# ethernet_usb.net
KiCad netlist of a schematic drawn in EAGLE
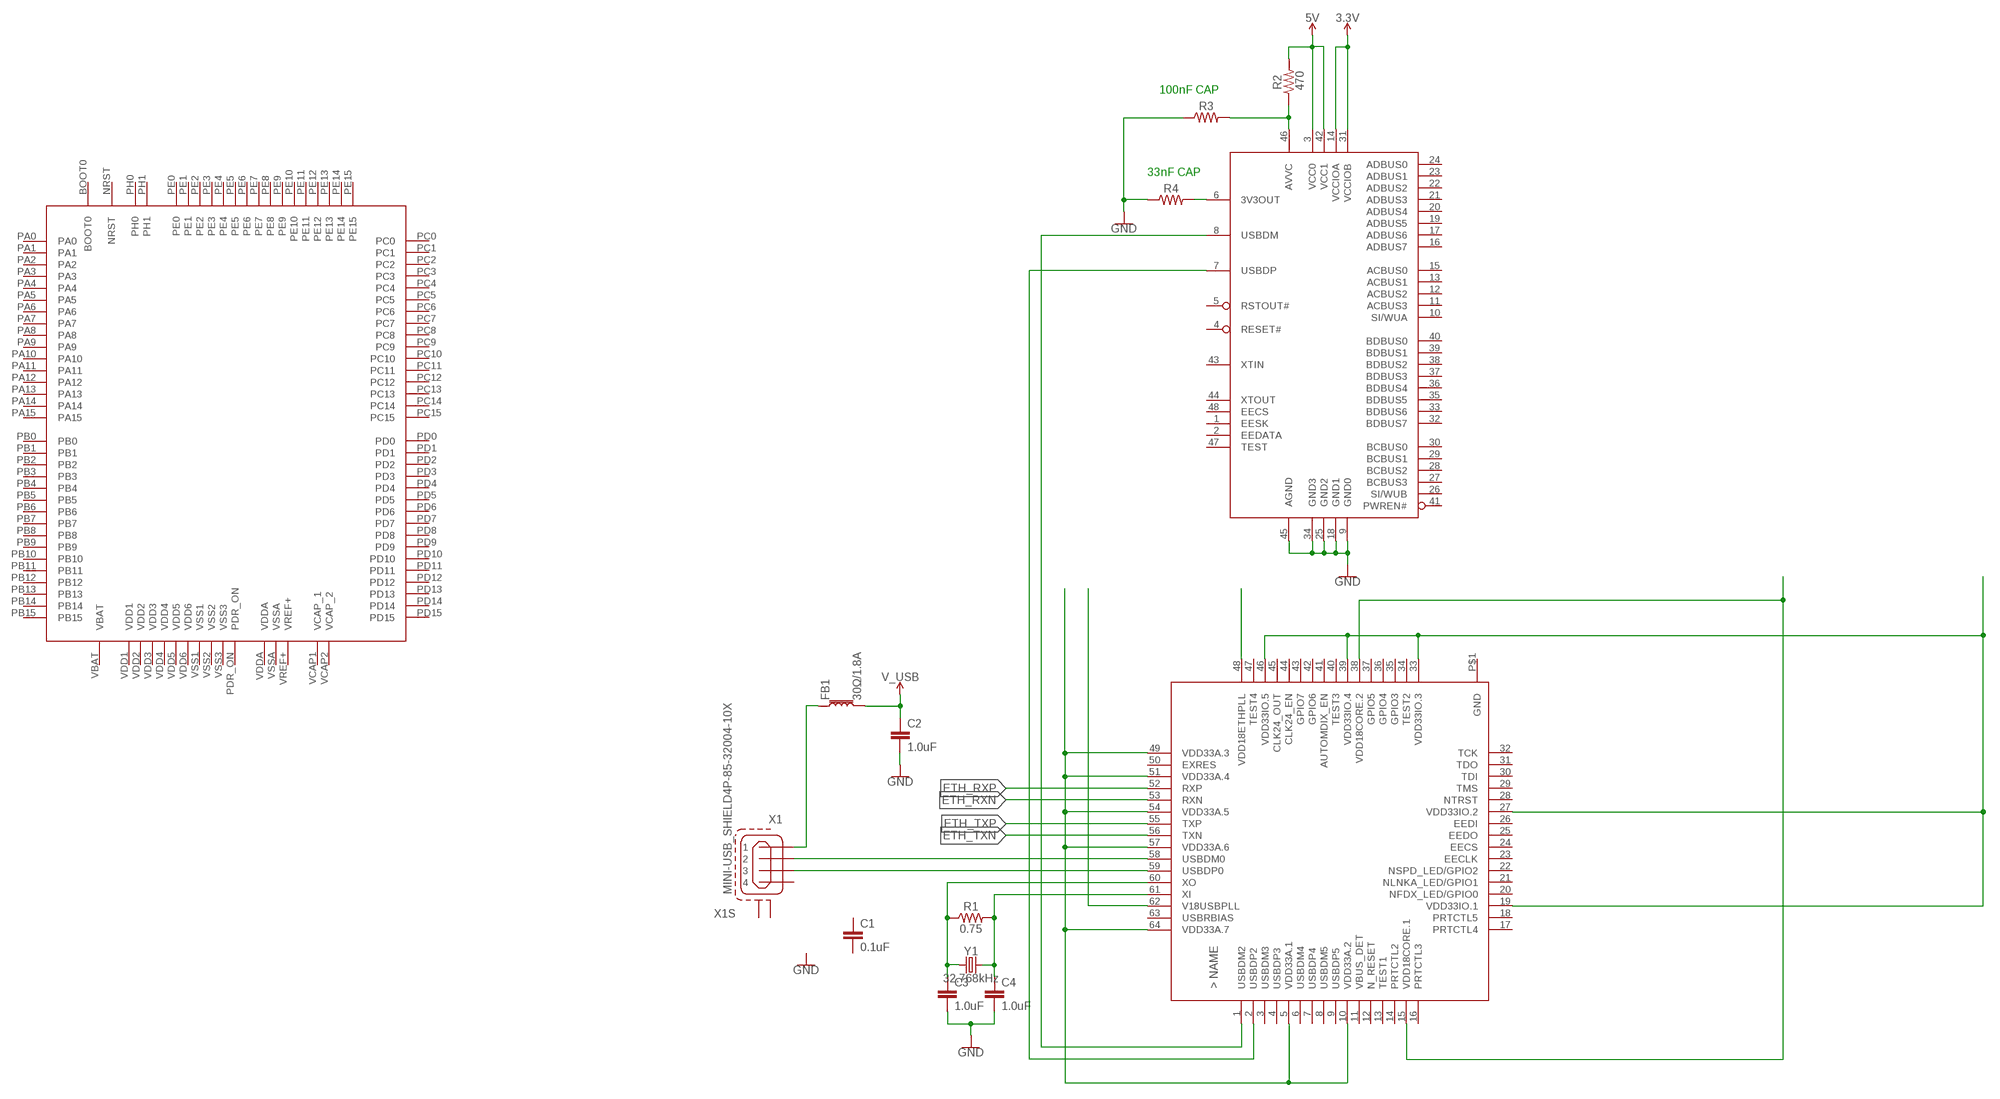
[diagram p0: schematic, sheet 1]

(export (version "E")
  (design (tool "Eeschema 10.0.6"))
  (components
    (comp (ref "C1")
      (value "0.1uF")
      (footprint "eagle-import:0603")
      (libsource (lib "eagle-import") (part "0.1UF-0603-25V-(+80/-20%)"))
    )
    (comp (ref "C2")
      (value "1.0uF")
      (footprint "eagle-import:1206")
      (libsource (lib "eagle-import") (part "1.0UF-1206-50V-10%"))
    )
    (comp (ref "C3")
      (value "1.0uF")
      (footprint "eagle-import:0805")
      (libsource (lib "eagle-import") (part "1.0UF-0805-25V-10%"))
    )
    (comp (ref "C4")
      (value "1.0uF")
      (footprint "eagle-import:0805")
      (libsource (lib "eagle-import") (part "1.0UF-0805-25V-10%"))
    )
    (comp (ref "FB1")
      (value "30Ω/1.8A")
      (footprint "eagle-import:0603")
      (libsource (lib "eagle-import") (part "FERRITE_BEAD-0603"))
    )
    (comp (ref "R1")
      (value "0.75")
      (footprint "eagle-import:0805")
      (libsource (lib "eagle-import") (part "0.75OHM-0805-1/4W-1%"))
    )
    (comp (ref "R2")
      (value "470")
      (footprint "eagle-import:0805")
      (libsource (lib "eagle-import") (part "RESISTOR0805"))
    )
    (comp (ref "R3")
      (value "RESISTOR0805")
      (footprint "eagle-import:0805")
      (libsource (lib "eagle-import") (part "RESISTOR0805"))
    )
    (comp (ref "R4")
      (value "RESISTOR0805")
      (footprint "eagle-import:0805")
      (libsource (lib "eagle-import") (part "RESISTOR0805"))
    )
    (comp (ref "U$1")
      (value "STM32F4V_100PIN_GENERIC")
      (footprint "eagle-import:LQFP100")
      (libsource (lib "eagle-import") (part "STM32F4V_100PIN_GENERIC"))
    )
    (comp (ref "U$2")
      (value "LAN9514")
      (footprint "eagle-import:QFN-64")
      (libsource (lib "eagle-import") (part "LAN9514"))
    )
    (comp (ref "U1")
      (value "FT2232L")
      (footprint "eagle-import:LQFP48")
      (libsource (lib "eagle-import") (part "FT2232L"))
    )
    (comp (ref "X1")
      (value "MINI-USB_SHIELD4P-85-32004-10X")
      (footprint "eagle-import:85-32004-10X")
      (libsource (lib "eagle-import") (part "MINI-USB_SHIELD4P-85-32004-10X"))
    )
    (comp (ref "Y1")
      (value "32.768kHz")
      (footprint "eagle-import:CRYSTAL-PTH-2X6-CYL")
      (libsource (lib "eagle-import") (part "CRYSTAL-32.768KHZPTH-2X6"))
    )
  )
  (nets
    (net (code "1") (name "3.3V") (class "Default")
      (node (ref "U1") (pin "14") (pinfunction "VCCIOA_14") (pintype "bidirectional"))
      (node (ref "U1") (pin "31") (pinfunction "VCCIOB_31") (pintype "bidirectional"))
    )
    (net (code "2") (name "5V") (class "Default")
      (node (ref "R2") (pin "2") (pinfunction "2_2") (pintype "passive"))
      (node (ref "U1") (pin "3") (pinfunction "VCC0_3") (pintype "bidirectional"))
      (node (ref "U1") (pin "42") (pinfunction "VCC1_42") (pintype "bidirectional"))
    )
    (net (code "3") (name "ETH_RXN") (class "Default")
      (node (ref "U$2") (pin "53") (pinfunction "RXN_53") (pintype "bidirectional"))
    )
    (net (code "4") (name "ETH_RXP") (class "Default")
      (node (ref "U$2") (pin "52") (pinfunction "RXP_52") (pintype "bidirectional"))
    )
    (net (code "5") (name "ETH_TXN") (class "Default")
      (node (ref "U$2") (pin "56") (pinfunction "TXN_56") (pintype "bidirectional"))
    )
    (net (code "6") (name "ETH_TXP") (class "Default")
      (node (ref "U$2") (pin "55") (pinfunction "TXP_55") (pintype "bidirectional"))
    )
    (net (code "7") (name "GND") (class "Default")
      (node (ref "C2") (pin "2") (pinfunction "2_2") (pintype "passive"))
      (node (ref "C3") (pin "2") (pinfunction "2_2") (pintype "passive"))
      (node (ref "C4") (pin "2") (pinfunction "2_2") (pintype "passive"))
      (node (ref "R3") (pin "1") (pinfunction "1_1") (pintype "passive"))
      (node (ref "R4") (pin "1") (pinfunction "1_1") (pintype "passive"))
      (node (ref "U1") (pin "18") (pinfunction "GND1_18") (pintype "bidirectional"))
      (node (ref "U1") (pin "25") (pinfunction "GND2_25") (pintype "bidirectional"))
      (node (ref "U1") (pin "34") (pinfunction "GND3_34") (pintype "bidirectional"))
      (node (ref "U1") (pin "45") (pinfunction "AGND_45") (pintype "bidirectional"))
      (node (ref "U1") (pin "9") (pinfunction "GND0_9") (pintype "bidirectional"))
    )
    (net (code "8") (name "Net-(FB1-Pad1)") (class "Default")
      (node (ref "FB1") (pin "1") (pinfunction "1_1") (pintype "passive"))
      (node (ref "X1") (pin "1") (pinfunction "1_1") (pintype "passive"))
    )
    (net (code "9") (name "Net-(U$2-USBDM0)") (class "Default")
      (node (ref "U$2") (pin "58") (pinfunction "USBDM0_58") (pintype "bidirectional"))
      (node (ref "X1") (pin "2") (pinfunction "2_2") (pintype "passive"))
    )
    (net (code "10") (name "Net-(U$2-USBDM2)") (class "Default")
      (node (ref "U$2") (pin "1") (pinfunction "USBDM2_1") (pintype "bidirectional"))
      (node (ref "U1") (pin "8") (pinfunction "USBDM_8") (pintype "bidirectional"))
    )
    (net (code "11") (name "Net-(U$2-USBDP0)") (class "Default")
      (node (ref "U$2") (pin "59") (pinfunction "USBDP0_59") (pintype "bidirectional"))
      (node (ref "X1") (pin "3") (pinfunction "3_3") (pintype "passive"))
    )
    (net (code "12") (name "Net-(U$2-USBDP2)") (class "Default")
      (node (ref "U$2") (pin "2") (pinfunction "USBDP2_2") (pintype "bidirectional"))
      (node (ref "U1") (pin "7") (pinfunction "USBDP_7") (pintype "bidirectional"))
    )
    (net (code "13") (name "Net-(U$2-VDD18CORE.1)") (class "Default")
      (node (ref "U$2") (pin "15") (pinfunction "VDD18CORE.1_15") (pintype "bidirectional"))
      (node (ref "U$2") (pin "38") (pinfunction "VDD18CORE.2_38") (pintype "bidirectional"))
    )
    (net (code "14") (name "Net-(U$2-VDD33A.1)") (class "Default")
      (node (ref "U$2") (pin "10") (pinfunction "VDD33A.2_10") (pintype "bidirectional"))
      (node (ref "U$2") (pin "49") (pinfunction "VDD33A.3_49") (pintype "bidirectional"))
      (node (ref "U$2") (pin "5") (pinfunction "VDD33A.1_5") (pintype "bidirectional"))
      (node (ref "U$2") (pin "51") (pinfunction "VDD33A.4_51") (pintype "bidirectional"))
      (node (ref "U$2") (pin "54") (pinfunction "VDD33A.5_54") (pintype "bidirectional"))
      (node (ref "U$2") (pin "57") (pinfunction "VDD33A.6_57") (pintype "bidirectional"))
      (node (ref "U$2") (pin "64") (pinfunction "VDD33A.7_64") (pintype "bidirectional"))
    )
    (net (code "15") (name "Net-(U$2-VDD33IO.1)") (class "Default")
      (node (ref "U$2") (pin "19") (pinfunction "VDD33IO.1_19") (pintype "bidirectional"))
      (node (ref "U$2") (pin "27") (pinfunction "VDD33IO.2_27") (pintype "bidirectional"))
      (node (ref "U$2") (pin "33") (pinfunction "VDD33IO.3_33") (pintype "bidirectional"))
      (node (ref "U$2") (pin "39") (pinfunction "VDD33IO.4_39") (pintype "bidirectional"))
      (node (ref "U$2") (pin "46") (pinfunction "VDD33IO.5_46") (pintype "bidirectional"))
    )
    (net (code "16") (name "Net-(U$2-XI)") (class "Default")
      (node (ref "C4") (pin "1") (pinfunction "1_1") (pintype "passive"))
      (node (ref "R1") (pin "2") (pinfunction "2_2") (pintype "passive"))
      (node (ref "U$2") (pin "61") (pinfunction "XI_61") (pintype "bidirectional"))
      (node (ref "Y1") (pin "2") (pinfunction "2_2") (pintype "passive"))
    )
    (net (code "17") (name "Net-(U$2-XO)") (class "Default")
      (node (ref "C3") (pin "1") (pinfunction "1_1") (pintype "passive"))
      (node (ref "R1") (pin "1") (pinfunction "1_1") (pintype "passive"))
      (node (ref "U$2") (pin "60") (pinfunction "XO_60") (pintype "bidirectional"))
      (node (ref "Y1") (pin "1") (pinfunction "1_1") (pintype "passive"))
    )
    (net (code "18") (name "Net-(U1-3V3OUT)") (class "Default")
      (node (ref "R4") (pin "2") (pinfunction "2_2") (pintype "passive"))
      (node (ref "U1") (pin "6") (pinfunction "3V3OUT_6") (pintype "bidirectional"))
    )
    (net (code "19") (name "Net-(U1-AVVC)") (class "Default")
      (node (ref "R2") (pin "1") (pinfunction "1_1") (pintype "passive"))
      (node (ref "R3") (pin "2") (pinfunction "2_2") (pintype "passive"))
      (node (ref "U1") (pin "46") (pinfunction "AVVC_46") (pintype "bidirectional"))
    )
    (net (code "20") (name "V_USB") (class "Default")
      (node (ref "C2") (pin "1") (pinfunction "1_1") (pintype "passive"))
      (node (ref "FB1") (pin "2") (pinfunction "2_2") (pintype "passive"))
    )
    (net (code "21") (name "unconnected-(C1-Pad1)") (class "Default")
      (node (ref "C1") (pin "1") (pinfunction "1_1") (pintype "passive"))
    )
    (net (code "22") (name "unconnected-(C1-Pad2)") (class "Default")
      (node (ref "C1") (pin "2") (pinfunction "2_2") (pintype "passive"))
    )
    (net (code "23") (name "unconnected-(U$1-PadBOOT0)") (class "Default")
      (node (ref "U$1") (pin "BOOT0") (pinfunction "BOOT0_BOOT0") (pintype "bidirectional"))
    )
    (net (code "24") (name "unconnected-(U$1-PadNRST)") (class "Default")
      (node (ref "U$1") (pin "NRST") (pinfunction "NRST_NRST") (pintype "bidirectional"))
    )
    (net (code "25") (name "unconnected-(U$1-PadPA0)") (class "Default")
      (node (ref "U$1") (pin "PA0") (pinfunction "PA0_PA0") (pintype "bidirectional"))
    )
    (net (code "26") (name "unconnected-(U$1-PadPA1)") (class "Default")
      (node (ref "U$1") (pin "PA1") (pinfunction "PA1_PA1") (pintype "bidirectional"))
    )
    (net (code "27") (name "unconnected-(U$1-PadPA2)") (class "Default")
      (node (ref "U$1") (pin "PA2") (pinfunction "PA2_PA2") (pintype "bidirectional"))
    )
    (net (code "28") (name "unconnected-(U$1-PadPA3)") (class "Default")
      (node (ref "U$1") (pin "PA3") (pinfunction "PA3_PA3") (pintype "bidirectional"))
    )
    (net (code "29") (name "unconnected-(U$1-PadPA4)") (class "Default")
      (node (ref "U$1") (pin "PA4") (pinfunction "PA4_PA4") (pintype "bidirectional"))
    )
    (net (code "30") (name "unconnected-(U$1-PadPA5)") (class "Default")
      (node (ref "U$1") (pin "PA5") (pinfunction "PA5_PA5") (pintype "bidirectional"))
    )
    (net (code "31") (name "unconnected-(U$1-PadPA6)") (class "Default")
      (node (ref "U$1") (pin "PA6") (pinfunction "PA6_PA6") (pintype "bidirectional"))
    )
    (net (code "32") (name "unconnected-(U$1-PadPA7)") (class "Default")
      (node (ref "U$1") (pin "PA7") (pinfunction "PA7_PA7") (pintype "bidirectional"))
    )
    (net (code "33") (name "unconnected-(U$1-PadPA8)") (class "Default")
      (node (ref "U$1") (pin "PA8") (pinfunction "PA8_PA8") (pintype "bidirectional"))
    )
    (net (code "34") (name "unconnected-(U$1-PadPA9)") (class "Default")
      (node (ref "U$1") (pin "PA9") (pinfunction "PA9_PA9") (pintype "bidirectional"))
    )
    (net (code "35") (name "unconnected-(U$1-PadPA10)") (class "Default")
      (node (ref "U$1") (pin "PA10") (pinfunction "PA10_PA10") (pintype "bidirectional"))
    )
    (net (code "36") (name "unconnected-(U$1-PadPA11)") (class "Default")
      (node (ref "U$1") (pin "PA11") (pinfunction "PA11_PA11") (pintype "bidirectional"))
    )
    (net (code "37") (name "unconnected-(U$1-PadPA12)") (class "Default")
      (node (ref "U$1") (pin "PA12") (pinfunction "PA12_PA12") (pintype "bidirectional"))
    )
    (net (code "38") (name "unconnected-(U$1-PadPA13)") (class "Default")
      (node (ref "U$1") (pin "PA13") (pinfunction "PA13_PA13") (pintype "bidirectional"))
    )
    (net (code "39") (name "unconnected-(U$1-PadPA14)") (class "Default")
      (node (ref "U$1") (pin "PA14") (pinfunction "PA14_PA14") (pintype "bidirectional"))
    )
    (net (code "40") (name "unconnected-(U$1-PadPA15)") (class "Default")
      (node (ref "U$1") (pin "PA15") (pinfunction "PA15_PA15") (pintype "bidirectional"))
    )
    (net (code "41") (name "unconnected-(U$1-PadPB0)") (class "Default")
      (node (ref "U$1") (pin "PB0") (pinfunction "PB0_PB0") (pintype "bidirectional"))
    )
    (net (code "42") (name "unconnected-(U$1-PadPB1)") (class "Default")
      (node (ref "U$1") (pin "PB1") (pinfunction "PB1_PB1") (pintype "bidirectional"))
    )
    (net (code "43") (name "unconnected-(U$1-PadPB2)") (class "Default")
      (node (ref "U$1") (pin "PB2") (pinfunction "PB2_PB2") (pintype "bidirectional"))
    )
    (net (code "44") (name "unconnected-(U$1-PadPB3)") (class "Default")
      (node (ref "U$1") (pin "PB3") (pinfunction "PB3_PB3") (pintype "bidirectional"))
    )
    (net (code "45") (name "unconnected-(U$1-PadPB4)") (class "Default")
      (node (ref "U$1") (pin "PB4") (pinfunction "PB4_PB4") (pintype "bidirectional"))
    )
    (net (code "46") (name "unconnected-(U$1-PadPB5)") (class "Default")
      (node (ref "U$1") (pin "PB5") (pinfunction "PB5_PB5") (pintype "bidirectional"))
    )
    (net (code "47") (name "unconnected-(U$1-PadPB6)") (class "Default")
      (node (ref "U$1") (pin "PB6") (pinfunction "PB6_PB6") (pintype "bidirectional"))
    )
    (net (code "48") (name "unconnected-(U$1-PadPB7)") (class "Default")
      (node (ref "U$1") (pin "PB7") (pinfunction "PB7_PB7") (pintype "bidirectional"))
    )
    (net (code "49") (name "unconnected-(U$1-PadPB8)") (class "Default")
      (node (ref "U$1") (pin "PB8") (pinfunction "PB8_PB8") (pintype "bidirectional"))
    )
    (net (code "50") (name "unconnected-(U$1-PadPB9)") (class "Default")
      (node (ref "U$1") (pin "PB9") (pinfunction "PB9_PB9") (pintype "bidirectional"))
    )
    (net (code "51") (name "unconnected-(U$1-PadPB10)") (class "Default")
      (node (ref "U$1") (pin "PB10") (pinfunction "PB10_PB10") (pintype "bidirectional"))
    )
    (net (code "52") (name "unconnected-(U$1-PadPB11)") (class "Default")
      (node (ref "U$1") (pin "PB11") (pinfunction "PB11_PB11") (pintype "bidirectional"))
    )
    (net (code "53") (name "unconnected-(U$1-PadPB12)") (class "Default")
      (node (ref "U$1") (pin "PB12") (pinfunction "PB12_PB12") (pintype "bidirectional"))
    )
    (net (code "54") (name "unconnected-(U$1-PadPB13)") (class "Default")
      (node (ref "U$1") (pin "PB13") (pinfunction "PB13_PB13") (pintype "bidirectional"))
    )
    (net (code "55") (name "unconnected-(U$1-PadPB14)") (class "Default")
      (node (ref "U$1") (pin "PB14") (pinfunction "PB14_PB14") (pintype "bidirectional"))
    )
    (net (code "56") (name "unconnected-(U$1-PadPB15)") (class "Default")
      (node (ref "U$1") (pin "PB15") (pinfunction "PB15_PB15") (pintype "bidirectional"))
    )
    (net (code "57") (name "unconnected-(U$1-PadPC0)") (class "Default")
      (node (ref "U$1") (pin "PC0") (pinfunction "PC0_PC0") (pintype "bidirectional"))
    )
    (net (code "58") (name "unconnected-(U$1-PadPC1)") (class "Default")
      (node (ref "U$1") (pin "PC1") (pinfunction "PC1_PC1") (pintype "bidirectional"))
    )
    (net (code "59") (name "unconnected-(U$1-PadPC2)") (class "Default")
      (node (ref "U$1") (pin "PC2") (pinfunction "PC2_PC2") (pintype "bidirectional"))
    )
    (net (code "60") (name "unconnected-(U$1-PadPC3)") (class "Default")
      (node (ref "U$1") (pin "PC3") (pinfunction "PC3_PC3") (pintype "bidirectional"))
    )
    (net (code "61") (name "unconnected-(U$1-PadPC4)") (class "Default")
      (node (ref "U$1") (pin "PC4") (pinfunction "PC4_PC4") (pintype "bidirectional"))
    )
    (net (code "62") (name "unconnected-(U$1-PadPC5)") (class "Default")
      (node (ref "U$1") (pin "PC5") (pinfunction "PC5_PC5") (pintype "bidirectional"))
    )
    (net (code "63") (name "unconnected-(U$1-PadPC6)") (class "Default")
      (node (ref "U$1") (pin "PC6") (pinfunction "PC6_PC6") (pintype "bidirectional"))
    )
    (net (code "64") (name "unconnected-(U$1-PadPC7)") (class "Default")
      (node (ref "U$1") (pin "PC7") (pinfunction "PC7_PC7") (pintype "bidirectional"))
    )
    (net (code "65") (name "unconnected-(U$1-PadPC8)") (class "Default")
      (node (ref "U$1") (pin "PC8") (pinfunction "PC8_PC8") (pintype "bidirectional"))
    )
    (net (code "66") (name "unconnected-(U$1-PadPC9)") (class "Default")
      (node (ref "U$1") (pin "PC9") (pinfunction "PC9_PC9") (pintype "bidirectional"))
    )
    (net (code "67") (name "unconnected-(U$1-PadPC10)") (class "Default")
      (node (ref "U$1") (pin "PC10") (pinfunction "PC10_PC10") (pintype "bidirectional"))
    )
    (net (code "68") (name "unconnected-(U$1-PadPC11)") (class "Default")
      (node (ref "U$1") (pin "PC11") (pinfunction "PC11_PC11") (pintype "bidirectional"))
    )
    (net (code "69") (name "unconnected-(U$1-PadPC12)") (class "Default")
      (node (ref "U$1") (pin "PC12") (pinfunction "PC12_PC12") (pintype "bidirectional"))
    )
    (net (code "70") (name "unconnected-(U$1-PadPC13)") (class "Default")
      (node (ref "U$1") (pin "PC13") (pinfunction "PC13_PC13") (pintype "bidirectional"))
    )
    (net (code "71") (name "unconnected-(U$1-PadPC14)") (class "Default")
      (node (ref "U$1") (pin "PC14") (pinfunction "PC14_PC14") (pintype "bidirectional"))
    )
    (net (code "72") (name "unconnected-(U$1-PadPC15)") (class "Default")
      (node (ref "U$1") (pin "PC15") (pinfunction "PC15_PC15") (pintype "bidirectional"))
    )
    (net (code "73") (name "unconnected-(U$1-PadPD0)") (class "Default")
      (node (ref "U$1") (pin "PD0") (pinfunction "PD0_PD0") (pintype "bidirectional"))
    )
    (net (code "74") (name "unconnected-(U$1-PadPD1)") (class "Default")
      (node (ref "U$1") (pin "PD1") (pinfunction "PD1_PD1") (pintype "bidirectional"))
    )
    (net (code "75") (name "unconnected-(U$1-PadPD2)") (class "Default")
      (node (ref "U$1") (pin "PD2") (pinfunction "PD2_PD2") (pintype "bidirectional"))
    )
    (net (code "76") (name "unconnected-(U$1-PadPD3)") (class "Default")
      (node (ref "U$1") (pin "PD3") (pinfunction "PD3_PD3") (pintype "bidirectional"))
    )
    (net (code "77") (name "unconnected-(U$1-PadPD4)") (class "Default")
      (node (ref "U$1") (pin "PD4") (pinfunction "PD4_PD4") (pintype "bidirectional"))
    )
    (net (code "78") (name "unconnected-(U$1-PadPD5)") (class "Default")
      (node (ref "U$1") (pin "PD5") (pinfunction "PD5_PD5") (pintype "bidirectional"))
    )
    (net (code "79") (name "unconnected-(U$1-PadPD6)") (class "Default")
      (node (ref "U$1") (pin "PD6") (pinfunction "PD6_PD6") (pintype "bidirectional"))
    )
    (net (code "80") (name "unconnected-(U$1-PadPD7)") (class "Default")
      (node (ref "U$1") (pin "PD7") (pinfunction "PD7_PD7") (pintype "bidirectional"))
    )
    (net (code "81") (name "unconnected-(U$1-PadPD8)") (class "Default")
      (node (ref "U$1") (pin "PD8") (pinfunction "PD8_PD8") (pintype "bidirectional"))
    )
    (net (code "82") (name "unconnected-(U$1-PadPD9)") (class "Default")
      (node (ref "U$1") (pin "PD9") (pinfunction "PD9_PD9") (pintype "bidirectional"))
    )
    (net (code "83") (name "unconnected-(U$1-PadPD10)") (class "Default")
      (node (ref "U$1") (pin "PD10") (pinfunction "PD10_PD10") (pintype "bidirectional"))
    )
    (net (code "84") (name "unconnected-(U$1-PadPD11)") (class "Default")
      (node (ref "U$1") (pin "PD11") (pinfunction "PD11_PD11") (pintype "bidirectional"))
    )
    (net (code "85") (name "unconnected-(U$1-PadPD12)") (class "Default")
      (node (ref "U$1") (pin "PD12") (pinfunction "PD12_PD12") (pintype "bidirectional"))
    )
    (net (code "86") (name "unconnected-(U$1-PadPD13)") (class "Default")
      (node (ref "U$1") (pin "PD13") (pinfunction "PD13_PD13") (pintype "bidirectional"))
    )
    (net (code "87") (name "unconnected-(U$1-PadPD14)") (class "Default")
      (node (ref "U$1") (pin "PD14") (pinfunction "PD14_PD14") (pintype "bidirectional"))
    )
    (net (code "88") (name "unconnected-(U$1-PadPD15)") (class "Default")
      (node (ref "U$1") (pin "PD15") (pinfunction "PD15_PD15") (pintype "bidirectional"))
    )
    (net (code "89") (name "unconnected-(U$1-PadPDR_ON)") (class "Default")
      (node (ref "U$1") (pin "PDR_ON") (pinfunction "PDR_ON_PDR_ON") (pintype "bidirectional"))
    )
    (net (code "90") (name "unconnected-(U$1-PadPE0)") (class "Default")
      (node (ref "U$1") (pin "PE0") (pinfunction "PE0_PE0") (pintype "bidirectional"))
    )
    (net (code "91") (name "unconnected-(U$1-PadPE1)") (class "Default")
      (node (ref "U$1") (pin "PE1") (pinfunction "PE1_PE1") (pintype "bidirectional"))
    )
    (net (code "92") (name "unconnected-(U$1-PadPE2)") (class "Default")
      (node (ref "U$1") (pin "PE2") (pinfunction "PE2_PE2") (pintype "bidirectional"))
    )
    (net (code "93") (name "unconnected-(U$1-PadPE3)") (class "Default")
      (node (ref "U$1") (pin "PE3") (pinfunction "PE3_PE3") (pintype "bidirectional"))
    )
    (net (code "94") (name "unconnected-(U$1-PadPE4)") (class "Default")
      (node (ref "U$1") (pin "PE4") (pinfunction "PE4_PE4") (pintype "bidirectional"))
    )
    (net (code "95") (name "unconnected-(U$1-PadPE5)") (class "Default")
      (node (ref "U$1") (pin "PE5") (pinfunction "PE5_PE5") (pintype "bidirectional"))
    )
    (net (code "96") (name "unconnected-(U$1-PadPE6)") (class "Default")
      (node (ref "U$1") (pin "PE6") (pinfunction "PE6_PE6") (pintype "bidirectional"))
    )
    (net (code "97") (name "unconnected-(U$1-PadPE7)") (class "Default")
      (node (ref "U$1") (pin "PE7") (pinfunction "PE7_PE7") (pintype "bidirectional"))
    )
    (net (code "98") (name "unconnected-(U$1-PadPE8)") (class "Default")
      (node (ref "U$1") (pin "PE8") (pinfunction "PE8_PE8") (pintype "bidirectional"))
    )
    (net (code "99") (name "unconnected-(U$1-PadPE9)") (class "Default")
      (node (ref "U$1") (pin "PE9") (pinfunction "PE9_PE9") (pintype "bidirectional"))
    )
    (net (code "100") (name "unconnected-(U$1-PadPE10)") (class "Default")
      (node (ref "U$1") (pin "PE10") (pinfunction "PE10_PE10") (pintype "bidirectional"))
    )
    (net (code "101") (name "unconnected-(U$1-PadPE11)") (class "Default")
      (node (ref "U$1") (pin "PE11") (pinfunction "PE11_PE11") (pintype "bidirectional"))
    )
    (net (code "102") (name "unconnected-(U$1-PadPE12)") (class "Default")
      (node (ref "U$1") (pin "PE12") (pinfunction "PE12_PE12") (pintype "bidirectional"))
    )
    (net (code "103") (name "unconnected-(U$1-PadPE13)") (class "Default")
      (node (ref "U$1") (pin "PE13") (pinfunction "PE13_PE13") (pintype "bidirectional"))
    )
    (net (code "104") (name "unconnected-(U$1-PadPE14)") (class "Default")
      (node (ref "U$1") (pin "PE14") (pinfunction "PE14_PE14") (pintype "bidirectional"))
    )
    (net (code "105") (name "unconnected-(U$1-PadPE15)") (class "Default")
      (node (ref "U$1") (pin "PE15") (pinfunction "PE15_PE15") (pintype "bidirectional"))
    )
    (net (code "106") (name "unconnected-(U$1-PadPH0)") (class "Default")
      (node (ref "U$1") (pin "PH0") (pinfunction "PH0_PH0") (pintype "bidirectional"))
    )
    (net (code "107") (name "unconnected-(U$1-PadPH1)") (class "Default")
      (node (ref "U$1") (pin "PH1") (pinfunction "PH1_PH1") (pintype "bidirectional"))
    )
    (net (code "108") (name "unconnected-(U$1-PadVBAT)") (class "Default")
      (node (ref "U$1") (pin "VBAT") (pinfunction "VBAT_VBAT") (pintype "bidirectional"))
    )
    (net (code "109") (name "unconnected-(U$1-PadVDD1)") (class "Default")
      (node (ref "U$1") (pin "VDD1") (pinfunction "VDD1_VDD1") (pintype "bidirectional"))
    )
    (net (code "110") (name "unconnected-(U$1-PadVDD2)") (class "Default")
      (node (ref "U$1") (pin "VDD2") (pinfunction "VDD2_VDD2") (pintype "bidirectional"))
    )
    (net (code "111") (name "unconnected-(U$1-PadVDD3)") (class "Default")
      (node (ref "U$1") (pin "VDD3") (pinfunction "VDD3_VDD3") (pintype "bidirectional"))
    )
    (net (code "112") (name "unconnected-(U$1-PadVDD4)") (class "Default")
      (node (ref "U$1") (pin "VDD4") (pinfunction "VDD4_VDD4") (pintype "bidirectional"))
    )
    (net (code "113") (name "unconnected-(U$1-PadVDD5)") (class "Default")
      (node (ref "U$1") (pin "VDD5") (pinfunction "VDD5_VDD5") (pintype "bidirectional"))
    )
    (net (code "114") (name "unconnected-(U$1-PadVDD6)") (class "Default")
      (node (ref "U$1") (pin "VDD6") (pinfunction "VDD6_VDD6") (pintype "bidirectional"))
    )
    (net (code "115") (name "unconnected-(U$1-PadVDDA)") (class "Default")
      (node (ref "U$1") (pin "VDDA") (pinfunction "VDDA_VDDA") (pintype "bidirectional"))
    )
    (net (code "116") (name "unconnected-(U$1-PadVREF+)") (class "Default")
      (node (ref "U$1") (pin "VREF+") (pinfunction "VREF+_VREF+") (pintype "bidirectional"))
    )
    (net (code "117") (name "unconnected-(U$1-PadVSS1)") (class "Default")
      (node (ref "U$1") (pin "VSS1") (pinfunction "VSS1_VSS1") (pintype "bidirectional"))
    )
    (net (code "118") (name "unconnected-(U$1-PadVSS2)") (class "Default")
      (node (ref "U$1") (pin "VSS2") (pinfunction "VSS2_VSS2") (pintype "bidirectional"))
    )
    (net (code "119") (name "unconnected-(U$1-PadVSS3)") (class "Default")
      (node (ref "U$1") (pin "VSS3") (pinfunction "VSS3_VSS3") (pintype "bidirectional"))
    )
    (net (code "120") (name "unconnected-(U$1-PadVSSA)") (class "Default")
      (node (ref "U$1") (pin "VSSA") (pinfunction "VSSA_VSSA") (pintype "bidirectional"))
    )
    (net (code "121") (name "unconnected-(U$1-VCAP_1-PadVCAP1)") (class "Default")
      (node (ref "U$1") (pin "VCAP1") (pinfunction "VCAP_1_VCAP1") (pintype "bidirectional"))
    )
    (net (code "122") (name "unconnected-(U$1-VCAP_2-PadVCAP2)") (class "Default")
      (node (ref "U$1") (pin "VCAP2") (pinfunction "VCAP_2_VCAP2") (pintype "bidirectional"))
    )
    (net (code "123") (name "unconnected-(U$2-AUTOMDIX_EN-Pad41)") (class "Default")
      (node (ref "U$2") (pin "41") (pinfunction "AUTOMDIX_EN_41") (pintype "bidirectional"))
    )
    (net (code "124") (name "unconnected-(U$2-CLK24_EN-Pad44)") (class "Default")
      (node (ref "U$2") (pin "44") (pinfunction "CLK24_EN_44") (pintype "bidirectional"))
    )
    (net (code "125") (name "unconnected-(U$2-CLK24_OUT-Pad45)") (class "Default")
      (node (ref "U$2") (pin "45") (pinfunction "CLK24_OUT_45") (pintype "bidirectional"))
    )
    (net (code "126") (name "unconnected-(U$2-EECLK-Pad23)") (class "Default")
      (node (ref "U$2") (pin "23") (pinfunction "EECLK_23") (pintype "bidirectional"))
    )
    (net (code "127") (name "unconnected-(U$2-EECS-Pad24)") (class "Default")
      (node (ref "U$2") (pin "24") (pinfunction "EECS_24") (pintype "bidirectional"))
    )
    (net (code "128") (name "unconnected-(U$2-EEDI-Pad26)") (class "Default")
      (node (ref "U$2") (pin "26") (pinfunction "EEDI_26") (pintype "bidirectional"))
    )
    (net (code "129") (name "unconnected-(U$2-EEDO-Pad25)") (class "Default")
      (node (ref "U$2") (pin "25") (pinfunction "EEDO_25") (pintype "bidirectional"))
    )
    (net (code "130") (name "unconnected-(U$2-EXRES-Pad50)") (class "Default")
      (node (ref "U$2") (pin "50") (pinfunction "EXRES_50") (pintype "bidirectional"))
    )
    (net (code "131") (name "unconnected-(U$2-GND-PadP$1)") (class "Default")
      (node (ref "U$2") (pin "P$1") (pinfunction "GND_P$1") (pintype "bidirectional"))
    )
    (net (code "132") (name "unconnected-(U$2-GPIO3-Pad35)") (class "Default")
      (node (ref "U$2") (pin "35") (pinfunction "GPIO3_35") (pintype "bidirectional"))
    )
    (net (code "133") (name "unconnected-(U$2-GPIO4-Pad36)") (class "Default")
      (node (ref "U$2") (pin "36") (pinfunction "GPIO4_36") (pintype "bidirectional"))
    )
    (net (code "134") (name "unconnected-(U$2-GPIO5-Pad37)") (class "Default")
      (node (ref "U$2") (pin "37") (pinfunction "GPIO5_37") (pintype "bidirectional"))
    )
    (net (code "135") (name "unconnected-(U$2-GPIO6-Pad42)") (class "Default")
      (node (ref "U$2") (pin "42") (pinfunction "GPIO6_42") (pintype "bidirectional"))
    )
    (net (code "136") (name "unconnected-(U$2-GPIO7-Pad43)") (class "Default")
      (node (ref "U$2") (pin "43") (pinfunction "GPIO7_43") (pintype "bidirectional"))
    )
    (net (code "137") (name "unconnected-(U$2-NFDX_LED{slash}GPIO0-Pad20)") (class "Default")
      (node (ref "U$2") (pin "20") (pinfunction "NFDX_LED/GPIO0_20") (pintype "bidirectional"))
    )
    (net (code "138") (name "unconnected-(U$2-NLNKA_LED{slash}GPIO1-Pad21)") (class "Default")
      (node (ref "U$2") (pin "21") (pinfunction "NLNKA_LED/GPIO1_21") (pintype "bidirectional"))
    )
    (net (code "139") (name "unconnected-(U$2-NSPD_LED{slash}GPIO2-Pad22)") (class "Default")
      (node (ref "U$2") (pin "22") (pinfunction "NSPD_LED/GPIO2_22") (pintype "bidirectional"))
    )
    (net (code "140") (name "unconnected-(U$2-NTRST-Pad28)") (class "Default")
      (node (ref "U$2") (pin "28") (pinfunction "NTRST_28") (pintype "bidirectional"))
    )
    (net (code "141") (name "unconnected-(U$2-N_RESET-Pad12)") (class "Default")
      (node (ref "U$2") (pin "12") (pinfunction "N_RESET_12") (pintype "bidirectional"))
    )
    (net (code "142") (name "unconnected-(U$2-PRTCTL2-Pad14)") (class "Default")
      (node (ref "U$2") (pin "14") (pinfunction "PRTCTL2_14") (pintype "bidirectional"))
    )
    (net (code "143") (name "unconnected-(U$2-PRTCTL3-Pad16)") (class "Default")
      (node (ref "U$2") (pin "16") (pinfunction "PRTCTL3_16") (pintype "bidirectional"))
    )
    (net (code "144") (name "unconnected-(U$2-PRTCTL4-Pad17)") (class "Default")
      (node (ref "U$2") (pin "17") (pinfunction "PRTCTL4_17") (pintype "bidirectional"))
    )
    (net (code "145") (name "unconnected-(U$2-PRTCTL5-Pad18)") (class "Default")
      (node (ref "U$2") (pin "18") (pinfunction "PRTCTL5_18") (pintype "bidirectional"))
    )
    (net (code "146") (name "unconnected-(U$2-TCK-Pad32)") (class "Default")
      (node (ref "U$2") (pin "32") (pinfunction "TCK_32") (pintype "bidirectional"))
    )
    (net (code "147") (name "unconnected-(U$2-TDI-Pad30)") (class "Default")
      (node (ref "U$2") (pin "30") (pinfunction "TDI_30") (pintype "bidirectional"))
    )
    (net (code "148") (name "unconnected-(U$2-TDO-Pad31)") (class "Default")
      (node (ref "U$2") (pin "31") (pinfunction "TDO_31") (pintype "bidirectional"))
    )
    (net (code "149") (name "unconnected-(U$2-TEST1-Pad13)") (class "Default")
      (node (ref "U$2") (pin "13") (pinfunction "TEST1_13") (pintype "bidirectional"))
    )
    (net (code "150") (name "unconnected-(U$2-TEST2-Pad34)") (class "Default")
      (node (ref "U$2") (pin "34") (pinfunction "TEST2_34") (pintype "bidirectional"))
    )
    (net (code "151") (name "unconnected-(U$2-TEST3-Pad40)") (class "Default")
      (node (ref "U$2") (pin "40") (pinfunction "TEST3_40") (pintype "bidirectional"))
    )
    (net (code "152") (name "unconnected-(U$2-TEST4-Pad47)") (class "Default")
      (node (ref "U$2") (pin "47") (pinfunction "TEST4_47") (pintype "bidirectional"))
    )
    (net (code "153") (name "unconnected-(U$2-TMS-Pad29)") (class "Default")
      (node (ref "U$2") (pin "29") (pinfunction "TMS_29") (pintype "bidirectional"))
    )
    (net (code "154") (name "unconnected-(U$2-USBDM3-Pad3)") (class "Default")
      (node (ref "U$2") (pin "3") (pinfunction "USBDM3_3") (pintype "bidirectional"))
    )
    (net (code "155") (name "unconnected-(U$2-USBDM4-Pad6)") (class "Default")
      (node (ref "U$2") (pin "6") (pinfunction "USBDM4_6") (pintype "bidirectional"))
    )
    (net (code "156") (name "unconnected-(U$2-USBDM5-Pad8)") (class "Default")
      (node (ref "U$2") (pin "8") (pinfunction "USBDM5_8") (pintype "bidirectional"))
    )
    (net (code "157") (name "unconnected-(U$2-USBDP3-Pad4)") (class "Default")
      (node (ref "U$2") (pin "4") (pinfunction "USBDP3_4") (pintype "bidirectional"))
    )
    (net (code "158") (name "unconnected-(U$2-USBDP4-Pad7)") (class "Default")
      (node (ref "U$2") (pin "7") (pinfunction "USBDP4_7") (pintype "bidirectional"))
    )
    (net (code "159") (name "unconnected-(U$2-USBDP5-Pad9)") (class "Default")
      (node (ref "U$2") (pin "9") (pinfunction "USBDP5_9") (pintype "bidirectional"))
    )
    (net (code "160") (name "unconnected-(U$2-USBRBIAS-Pad63)") (class "Default")
      (node (ref "U$2") (pin "63") (pinfunction "USBRBIAS_63") (pintype "bidirectional"))
    )
    (net (code "161") (name "unconnected-(U$2-V18USBPLL-Pad62)") (class "Default")
      (node (ref "U$2") (pin "62") (pinfunction "V18USBPLL_62") (pintype "bidirectional"))
    )
    (net (code "162") (name "unconnected-(U$2-VBUS_DET-Pad11)") (class "Default")
      (node (ref "U$2") (pin "11") (pinfunction "VBUS_DET_11") (pintype "bidirectional"))
    )
    (net (code "163") (name "unconnected-(U$2-VDD18ETHPLL-Pad48)") (class "Default")
      (node (ref "U$2") (pin "48") (pinfunction "VDD18ETHPLL_48") (pintype "bidirectional"))
    )
    (net (code "164") (name "unconnected-(U1-ACBUS0-Pad15)") (class "Default")
      (node (ref "U1") (pin "15") (pinfunction "ACBUS0_15") (pintype "bidirectional"))
    )
    (net (code "165") (name "unconnected-(U1-ACBUS1-Pad13)") (class "Default")
      (node (ref "U1") (pin "13") (pinfunction "ACBUS1_13") (pintype "bidirectional"))
    )
    (net (code "166") (name "unconnected-(U1-ACBUS2-Pad12)") (class "Default")
      (node (ref "U1") (pin "12") (pinfunction "ACBUS2_12") (pintype "bidirectional"))
    )
    (net (code "167") (name "unconnected-(U1-ACBUS3-Pad11)") (class "Default")
      (node (ref "U1") (pin "11") (pinfunction "ACBUS3_11") (pintype "bidirectional"))
    )
    (net (code "168") (name "unconnected-(U1-ADBUS0-Pad24)") (class "Default")
      (node (ref "U1") (pin "24") (pinfunction "ADBUS0_24") (pintype "bidirectional"))
    )
    (net (code "169") (name "unconnected-(U1-ADBUS1-Pad23)") (class "Default")
      (node (ref "U1") (pin "23") (pinfunction "ADBUS1_23") (pintype "bidirectional"))
    )
    (net (code "170") (name "unconnected-(U1-ADBUS2-Pad22)") (class "Default")
      (node (ref "U1") (pin "22") (pinfunction "ADBUS2_22") (pintype "bidirectional"))
    )
    (net (code "171") (name "unconnected-(U1-ADBUS3-Pad21)") (class "Default")
      (node (ref "U1") (pin "21") (pinfunction "ADBUS3_21") (pintype "bidirectional"))
    )
    (net (code "172") (name "unconnected-(U1-ADBUS4-Pad20)") (class "Default")
      (node (ref "U1") (pin "20") (pinfunction "ADBUS4_20") (pintype "bidirectional"))
    )
    (net (code "173") (name "unconnected-(U1-ADBUS5-Pad19)") (class "Default")
      (node (ref "U1") (pin "19") (pinfunction "ADBUS5_19") (pintype "bidirectional"))
    )
    (net (code "174") (name "unconnected-(U1-ADBUS6-Pad17)") (class "Default")
      (node (ref "U1") (pin "17") (pinfunction "ADBUS6_17") (pintype "bidirectional"))
    )
    (net (code "175") (name "unconnected-(U1-ADBUS7-Pad16)") (class "Default")
      (node (ref "U1") (pin "16") (pinfunction "ADBUS7_16") (pintype "bidirectional"))
    )
    (net (code "176") (name "unconnected-(U1-BCBUS0-Pad30)") (class "Default")
      (node (ref "U1") (pin "30") (pinfunction "BCBUS0_30") (pintype "bidirectional"))
    )
    (net (code "177") (name "unconnected-(U1-BCBUS1-Pad29)") (class "Default")
      (node (ref "U1") (pin "29") (pinfunction "BCBUS1_29") (pintype "bidirectional"))
    )
    (net (code "178") (name "unconnected-(U1-BCBUS2-Pad28)") (class "Default")
      (node (ref "U1") (pin "28") (pinfunction "BCBUS2_28") (pintype "bidirectional"))
    )
    (net (code "179") (name "unconnected-(U1-BCBUS3-Pad27)") (class "Default")
      (node (ref "U1") (pin "27") (pinfunction "BCBUS3_27") (pintype "bidirectional"))
    )
    (net (code "180") (name "unconnected-(U1-BDBUS0-Pad40)") (class "Default")
      (node (ref "U1") (pin "40") (pinfunction "BDBUS0_40") (pintype "bidirectional"))
    )
    (net (code "181") (name "unconnected-(U1-BDBUS1-Pad39)") (class "Default")
      (node (ref "U1") (pin "39") (pinfunction "BDBUS1_39") (pintype "bidirectional"))
    )
    (net (code "182") (name "unconnected-(U1-BDBUS2-Pad38)") (class "Default")
      (node (ref "U1") (pin "38") (pinfunction "BDBUS2_38") (pintype "bidirectional"))
    )
    (net (code "183") (name "unconnected-(U1-BDBUS3-Pad37)") (class "Default")
      (node (ref "U1") (pin "37") (pinfunction "BDBUS3_37") (pintype "bidirectional"))
    )
    (net (code "184") (name "unconnected-(U1-BDBUS4-Pad36)") (class "Default")
      (node (ref "U1") (pin "36") (pinfunction "BDBUS4_36") (pintype "bidirectional"))
    )
    (net (code "185") (name "unconnected-(U1-BDBUS5-Pad35)") (class "Default")
      (node (ref "U1") (pin "35") (pinfunction "BDBUS5_35") (pintype "bidirectional"))
    )
    (net (code "186") (name "unconnected-(U1-BDBUS6-Pad33)") (class "Default")
      (node (ref "U1") (pin "33") (pinfunction "BDBUS6_33") (pintype "bidirectional"))
    )
    (net (code "187") (name "unconnected-(U1-BDBUS7-Pad32)") (class "Default")
      (node (ref "U1") (pin "32") (pinfunction "BDBUS7_32") (pintype "bidirectional"))
    )
    (net (code "188") (name "unconnected-(U1-EECS-Pad48)") (class "Default")
      (node (ref "U1") (pin "48") (pinfunction "EECS_48") (pintype "bidirectional"))
    )
    (net (code "189") (name "unconnected-(U1-EEDATA-Pad2)") (class "Default")
      (node (ref "U1") (pin "2") (pinfunction "EEDATA_2") (pintype "bidirectional"))
    )
    (net (code "190") (name "unconnected-(U1-EESK-Pad1)") (class "Default")
      (node (ref "U1") (pin "1") (pinfunction "EESK_1") (pintype "bidirectional"))
    )
    (net (code "191") (name "unconnected-(U1-PWREN#-Pad41)") (class "Default")
      (node (ref "U1") (pin "41") (pinfunction "PWREN#_41") (pintype "bidirectional"))
    )
    (net (code "192") (name "unconnected-(U1-RESET#-Pad4)") (class "Default")
      (node (ref "U1") (pin "4") (pinfunction "RESET#_4") (pintype "bidirectional"))
    )
    (net (code "193") (name "unconnected-(U1-RSTOUT#-Pad5)") (class "Default")
      (node (ref "U1") (pin "5") (pinfunction "RSTOUT#_5") (pintype "bidirectional"))
    )
    (net (code "194") (name "unconnected-(U1-SI{slash}WUA-Pad10)") (class "Default")
      (node (ref "U1") (pin "10") (pinfunction "SI/WUA_10") (pintype "bidirectional"))
    )
    (net (code "195") (name "unconnected-(U1-SI{slash}WUB-Pad26)") (class "Default")
      (node (ref "U1") (pin "26") (pinfunction "SI/WUB_26") (pintype "bidirectional"))
    )
    (net (code "196") (name "unconnected-(U1-TEST-Pad47)") (class "Default")
      (node (ref "U1") (pin "47") (pinfunction "TEST_47") (pintype "bidirectional"))
    )
    (net (code "197") (name "unconnected-(U1-XTIN-Pad43)") (class "Default")
      (node (ref "U1") (pin "43") (pinfunction "XTIN_43") (pintype "bidirectional"))
    )
    (net (code "198") (name "unconnected-(U1-XTOUT-Pad44)") (class "Default")
      (node (ref "U1") (pin "44") (pinfunction "XTOUT_44") (pintype "bidirectional"))
    )
    (net (code "199") (name "unconnected-(X1-Pad4)") (class "Default")
      (node (ref "X1") (pin "4") (pinfunction "4_4") (pintype "passive"))
    )
    (net (code "200") (name "unconnected-(X1B-S1-PadM1)") (class "Default")
      (node (ref "X1") (pin "M1") (pinfunction "S1_M1") (pintype "passive"))
    )
    (net (code "201") (name "unconnected-(X1B-S2-PadM2)") (class "Default")
      (node (ref "X1") (pin "M2") (pinfunction "S2_M2") (pintype "passive"))
    )
  )
)
